# tsc.net
KiCad netlist of a schematic drawn in EAGLE
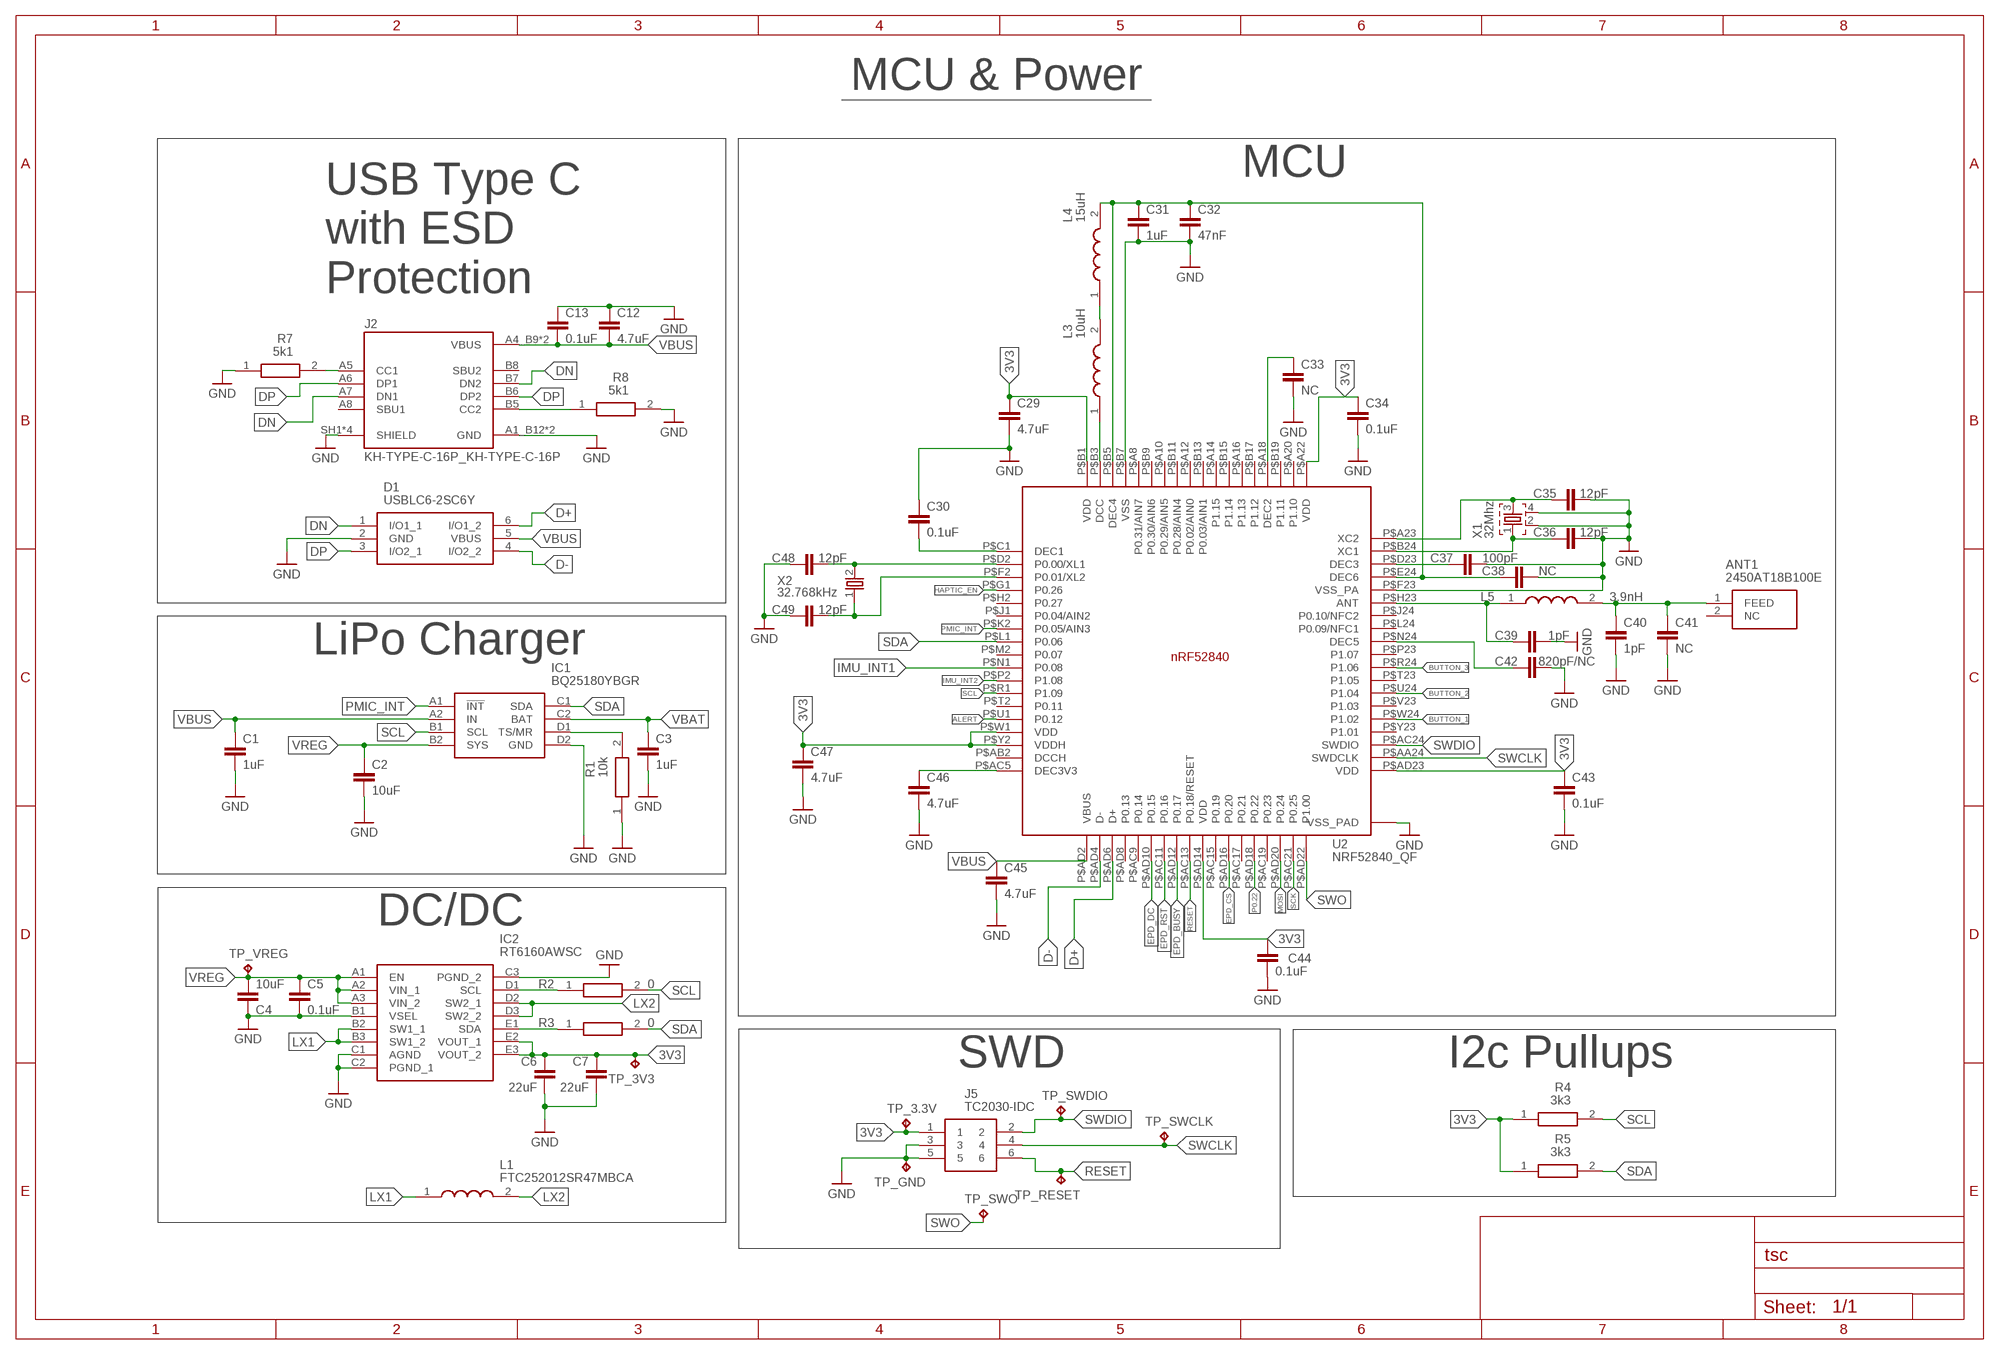
[diagram p0: schematic, sheet 1, part 1 of 2]
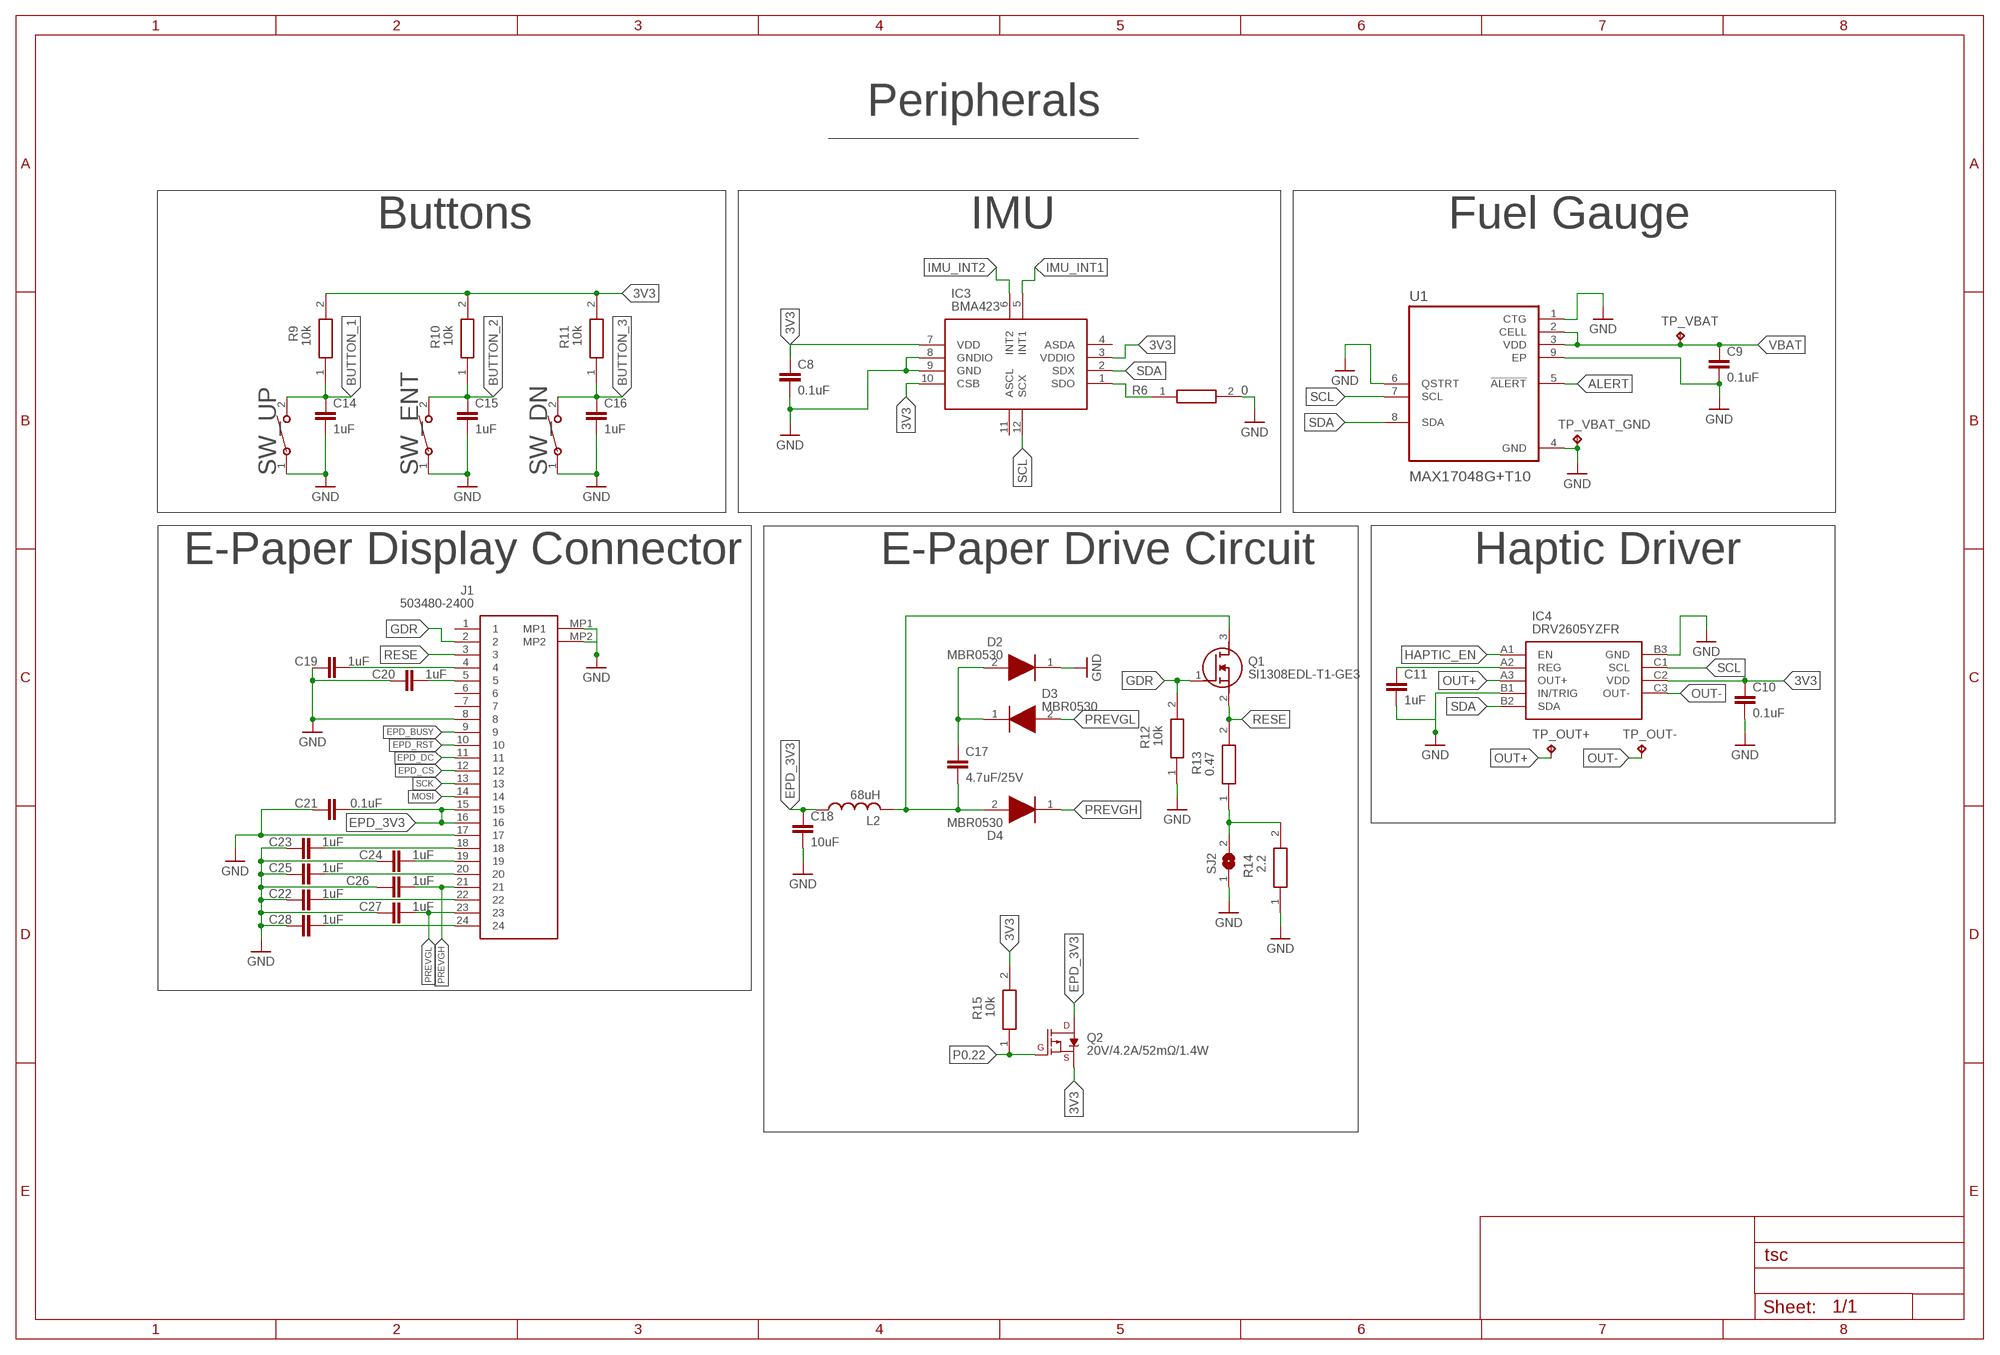
[diagram p1: schematic, sheet 1, part 2 of 2]

(export (version "E")
  (design (tool "Eeschema 10.0.6"))
  (components
    (comp (ref "ANT1")
      (value "2450AT18B100E")
      (footprint "eagle-import:2450AT18B100E_ANTC3216X140N")
      (fields (field (name "MOUSER_PART_NUMBER") "609-2450AT18B100E"))
      (libsource (lib "eagle-import") (part "2450AT18B100E_2450AT18B100E"))
    )
    (comp (ref "C1")
      (value "1uF")
      (footprint "eagle-import:NORDIC_NRF_3_RESC0402_N")
      (libsource (lib "eagle-import") (part "NORDIC_NRF_3_CAPACITOR_0402_N"))
    )
    (comp (ref "C2")
      (value "10uF")
      (footprint "eagle-import:NORDIC_NRF_3_RESC0402_N")
      (libsource (lib "eagle-import") (part "NORDIC_NRF_3_CAPACITOR_0402_N"))
    )
    (comp (ref "C3")
      (value "1uF")
      (footprint "eagle-import:NORDIC_NRF_3_RESC0402_N")
      (libsource (lib "eagle-import") (part "NORDIC_NRF_3_CAPACITOR_0402_N"))
    )
    (comp (ref "C4")
      (value "10uF")
      (footprint "eagle-import:NORDIC_NRF_3_RESC0402_N")
      (libsource (lib "eagle-import") (part "NORDIC_NRF_3_CAPACITOR_0402_N"))
    )
    (comp (ref "C5")
      (value "0.1uF")
      (footprint "eagle-import:NORDIC_NRF_3_RESC0201_N")
      (libsource (lib "eagle-import") (part "NORDIC_NRF_3_CAPACITOR_0201_N"))
    )
    (comp (ref "C6")
      (value "22uF")
      (footprint "eagle-import:NORDIC_NRF_3_RESC0402_N")
      (libsource (lib "eagle-import") (part "NORDIC_NRF_3_CAPACITOR_0402_N"))
    )
    (comp (ref "C7")
      (value "22uF")
      (footprint "eagle-import:NORDIC_NRF_3_RESC0402_N")
      (libsource (lib "eagle-import") (part "NORDIC_NRF_3_CAPACITOR_0402_N"))
    )
    (comp (ref "C8")
      (value "0.1uF")
      (footprint "eagle-import:NORDIC_NRF_3_RESC0201_N")
      (libsource (lib "eagle-import") (part "NORDIC_NRF_3_CAPACITOR_0201_N"))
    )
    (comp (ref "C9")
      (value "0.1uF")
      (footprint "eagle-import:NORDIC_NRF_3_RESC0201_N")
      (libsource (lib "eagle-import") (part "NORDIC_NRF_3_CAPACITOR_0201_N"))
    )
    (comp (ref "C10")
      (value "0.1uF")
      (footprint "eagle-import:NORDIC_NRF_3_RESC0201_N")
      (libsource (lib "eagle-import") (part "NORDIC_NRF_3_CAPACITOR_0201_N"))
    )
    (comp (ref "C11")
      (value "1uF")
      (footprint "eagle-import:NORDIC_NRF_3_RESC0402_N")
      (libsource (lib "eagle-import") (part "NORDIC_NRF_3_CAPACITOR_0402_N"))
    )
    (comp (ref "C12")
      (value "4.7uF")
      (footprint "eagle-import:NORDIC_NRF_3_RESC0402_N")
      (libsource (lib "eagle-import") (part "NORDIC_NRF_3_CAPACITOR_0402_N"))
    )
    (comp (ref "C13")
      (value "0.1uF")
      (footprint "eagle-import:NORDIC_NRF_3_RESC0201_N")
      (libsource (lib "eagle-import") (part "NORDIC_NRF_3_CAPACITOR_0201_N"))
    )
    (comp (ref "C14")
      (value "1uF")
      (footprint "eagle-import:NORDIC_NRF_3_RESC0402_N")
      (libsource (lib "eagle-import") (part "NORDIC_NRF_3_CAPACITOR_0402_N"))
    )
    (comp (ref "C15")
      (value "1uF")
      (footprint "eagle-import:NORDIC_NRF_3_RESC0402_N")
      (libsource (lib "eagle-import") (part "NORDIC_NRF_3_CAPACITOR_0402_N"))
    )
    (comp (ref "C16")
      (value "1uF")
      (footprint "eagle-import:NORDIC_NRF_3_RESC0402_N")
      (libsource (lib "eagle-import") (part "NORDIC_NRF_3_CAPACITOR_0402_N"))
    )
    (comp (ref "C17")
      (value "4.7uF/25V")
      (footprint "eagle-import:NORDIC_NRF_3_RESC0402_N")
      (libsource (lib "eagle-import") (part "NORDIC_NRF_3_CAPACITOR_0402_N"))
    )
    (comp (ref "C18")
      (value "10uF")
      (footprint "eagle-import:NORDIC_NRF_3_RESC0402_N")
      (libsource (lib "eagle-import") (part "NORDIC_NRF_3_CAPACITOR_0402_N"))
    )
    (comp (ref "C19")
      (value "1uF")
      (footprint "eagle-import:NORDIC_NRF_3_RESC0402_N")
      (libsource (lib "eagle-import") (part "NORDIC_NRF_3_CAPACITOR_0402_N"))
    )
    (comp (ref "C20")
      (value "1uF")
      (footprint "eagle-import:NORDIC_NRF_3_RESC0402_N")
      (libsource (lib "eagle-import") (part "NORDIC_NRF_3_CAPACITOR_0402_N"))
    )
    (comp (ref "C21")
      (value "0.1uF")
      (footprint "eagle-import:NORDIC_NRF_3_RESC0201_N")
      (libsource (lib "eagle-import") (part "NORDIC_NRF_3_CAPACITOR_0201_N"))
    )
    (comp (ref "C22")
      (value "1uF")
      (footprint "eagle-import:NORDIC_NRF_3_RESC0402_N")
      (libsource (lib "eagle-import") (part "NORDIC_NRF_3_CAPACITOR_0402_N"))
    )
    (comp (ref "C23")
      (value "1uF")
      (footprint "eagle-import:NORDIC_NRF_3_RESC0402_N")
      (libsource (lib "eagle-import") (part "NORDIC_NRF_3_CAPACITOR_0402_N"))
    )
    (comp (ref "C24")
      (value "1uF")
      (footprint "eagle-import:NORDIC_NRF_3_RESC0402_N")
      (libsource (lib "eagle-import") (part "NORDIC_NRF_3_CAPACITOR_0402_N"))
    )
    (comp (ref "C25")
      (value "1uF")
      (footprint "eagle-import:NORDIC_NRF_3_RESC0402_N")
      (libsource (lib "eagle-import") (part "NORDIC_NRF_3_CAPACITOR_0402_N"))
    )
    (comp (ref "C26")
      (value "1uF")
      (footprint "eagle-import:NORDIC_NRF_3_RESC0402_N")
      (libsource (lib "eagle-import") (part "NORDIC_NRF_3_CAPACITOR_0402_N"))
    )
    (comp (ref "C27")
      (value "1uF")
      (footprint "eagle-import:NORDIC_NRF_3_RESC0402_N")
      (libsource (lib "eagle-import") (part "NORDIC_NRF_3_CAPACITOR_0402_N"))
    )
    (comp (ref "C28")
      (value "1uF")
      (footprint "eagle-import:NORDIC_NRF_3_RESC0402_N")
      (libsource (lib "eagle-import") (part "NORDIC_NRF_3_CAPACITOR_0402_N"))
    )
    (comp (ref "C29")
      (value "4.7uF")
      (footprint "eagle-import:NORDIC_NRF_3_RESC0402_N")
      (libsource (lib "eagle-import") (part "NORDIC_NRF_3_CAPACITOR_0402_N"))
    )
    (comp (ref "C30")
      (value "0.1uF")
      (footprint "eagle-import:NORDIC_NRF_3_RESC0201_N")
      (libsource (lib "eagle-import") (part "NORDIC_NRF_3_CAPACITOR_0201_N"))
    )
    (comp (ref "C31")
      (value "1uF")
      (footprint "eagle-import:NORDIC_NRF_3_RESC0402_N")
      (libsource (lib "eagle-import") (part "NORDIC_NRF_3_CAPACITOR_0402_N"))
    )
    (comp (ref "C32")
      (value "47nF")
      (footprint "eagle-import:NORDIC_NRF_3_RESC0201_N")
      (libsource (lib "eagle-import") (part "NORDIC_NRF_3_CAPACITOR_0201_N"))
    )
    (comp (ref "C33")
      (value "NC")
      (footprint "eagle-import:NORDIC_NRF_3_RESC0201_N")
      (libsource (lib "eagle-import") (part "NORDIC_NRF_3_CAPACITOR_0201_N"))
    )
    (comp (ref "C34")
      (value "0.1uF")
      (footprint "eagle-import:NORDIC_NRF_3_RESC0201_N")
      (libsource (lib "eagle-import") (part "NORDIC_NRF_3_CAPACITOR_0201_N"))
    )
    (comp (ref "C35")
      (value "12pF")
      (footprint "eagle-import:NORDIC_NRF_3_RESC0201_N")
      (libsource (lib "eagle-import") (part "NORDIC_NRF_3_CAPACITOR_0201_N"))
    )
    (comp (ref "C36")
      (value "12pF")
      (footprint "eagle-import:NORDIC_NRF_3_RESC0201_N")
      (libsource (lib "eagle-import") (part "NORDIC_NRF_3_CAPACITOR_0201_N"))
    )
    (comp (ref "C37")
      (value "100pF")
      (footprint "eagle-import:NORDIC_NRF_3_RESC0201_N")
      (libsource (lib "eagle-import") (part "NORDIC_NRF_3_CAPACITOR_0201_N"))
    )
    (comp (ref "C38")
      (value "NC")
      (footprint "eagle-import:NORDIC_NRF_3_RESC0201_N")
      (libsource (lib "eagle-import") (part "NORDIC_NRF_3_CAPACITOR_0201_N"))
    )
    (comp (ref "C39")
      (value "1pF")
      (footprint "eagle-import:NORDIC_NRF_3_RESC0201_N")
      (libsource (lib "eagle-import") (part "NORDIC_NRF_3_CAPACITOR_0201_N"))
    )
    (comp (ref "C40")
      (value "1pF")
      (footprint "eagle-import:NORDIC_NRF_3_RESC0201_N")
      (libsource (lib "eagle-import") (part "NORDIC_NRF_3_CAPACITOR_0201_N"))
    )
    (comp (ref "C41")
      (value "NC")
      (footprint "eagle-import:NORDIC_NRF_3_RESC0201_N")
      (libsource (lib "eagle-import") (part "NORDIC_NRF_3_CAPACITOR_0201_N"))
    )
    (comp (ref "C42")
      (value "820pF/NC")
      (footprint "eagle-import:NORDIC_NRF_3_RESC0201_N")
      (libsource (lib "eagle-import") (part "NORDIC_NRF_3_CAPACITOR_0201_N"))
    )
    (comp (ref "C43")
      (value "0.1uF")
      (footprint "eagle-import:NORDIC_NRF_3_RESC0201_N")
      (libsource (lib "eagle-import") (part "NORDIC_NRF_3_CAPACITOR_0201_N"))
    )
    (comp (ref "C44")
      (value "0.1uF")
      (footprint "eagle-import:NORDIC_NRF_3_RESC0201_N")
      (libsource (lib "eagle-import") (part "NORDIC_NRF_3_CAPACITOR_0201_N"))
    )
    (comp (ref "C45")
      (value "4.7uF")
      (footprint "eagle-import:NORDIC_NRF_3_RESC0402_N")
      (libsource (lib "eagle-import") (part "NORDIC_NRF_3_CAPACITOR_0402_N"))
    )
    (comp (ref "C46")
      (value "4.7uF")
      (footprint "eagle-import:NORDIC_NRF_3_RESC0402_N")
      (libsource (lib "eagle-import") (part "NORDIC_NRF_3_CAPACITOR_0402_N"))
    )
    (comp (ref "C47")
      (value "4.7uF")
      (footprint "eagle-import:NORDIC_NRF_3_RESC0402_N")
      (libsource (lib "eagle-import") (part "NORDIC_NRF_3_CAPACITOR_0402_N"))
    )
    (comp (ref "C48")
      (value "12pF")
      (footprint "eagle-import:NORDIC_NRF_3_RESC0201_N")
      (libsource (lib "eagle-import") (part "NORDIC_NRF_3_CAPACITOR_0201_N"))
    )
    (comp (ref "C49")
      (value "12pF")
      (footprint "eagle-import:NORDIC_NRF_3_RESC0201_N")
      (libsource (lib "eagle-import") (part "NORDIC_NRF_3_CAPACITOR_0201_N"))
    )
    (comp (ref "D1")
      (value "USBLC6-2SC6Y")
      (footprint "eagle-import:ESP32_C6_LIBRARY_3_SOT95P280X145-6N")
      (fields (field (name "MF") "STMicroelectronics"))
      (libsource (lib "eagle-import") (part "ESP32_C6_LIBRARY_3_USBLC6-2SC6Y"))
    )
    (comp (ref "D2")
      (value "MBR0530")
      (footprint "eagle-import:ESP32_C6_LIBRARY_5_SOD3716X135N")
      (fields (field (name "MF") "ON Semiconductor"))
      (libsource (lib "eagle-import") (part "ESP32_C6_LIBRARY_5_MBR0530"))
    )
    (comp (ref "D3")
      (value "MBR0530")
      (footprint "eagle-import:ESP32_C6_LIBRARY_5_SOD3716X135N")
      (fields (field (name "MF") "ON Semiconductor"))
      (libsource (lib "eagle-import") (part "ESP32_C6_LIBRARY_5_MBR0530"))
    )
    (comp (ref "D4")
      (value "MBR0530")
      (footprint "eagle-import:ESP32_C6_LIBRARY_5_SOD3716X135N")
      (fields (field (name "MF") "ON Semiconductor"))
      (libsource (lib "eagle-import") (part "ESP32_C6_LIBRARY_5_MBR0530"))
    )
    (comp (ref "IC1")
      (value "BQ25180YBGR")
      (footprint "eagle-import:BQ25180YBGR_BGA8C40P2X4_100X155X50")
      (fields (field (name "MOUSER_PART_NUMBER") "595-BQ25180YBGR"))
      (libsource (lib "eagle-import") (part "BQ25180YBGR_BQ25180YBGR"))
    )
    (comp (ref "IC2")
      (value "RT6160AWSC")
      (footprint "eagle-import:RT6160AWSC_BGA15C40P3X5_140X230X60")
      (fields (field (name "MOUSER_PART_NUMBER") "835-RT6160AWSC"))
      (libsource (lib "eagle-import") (part "RT6160AWSC_RT6160AWSC"))
    )
    (comp (ref "IC3")
      (value "BMA423")
      (footprint "eagle-import:BMA423_BMA423")
      (fields (field (name "MOUSER_PART_NUMBER") "262-BMA423"))
      (libsource (lib "eagle-import") (part "BMA423_BMA423"))
    )
    (comp (ref "IC4")
      (value "DRV2605YZFR")
      (footprint "eagle-import:DRV2605YZFR_BGA9C50P3X3_144X144X62")
      (libsource (lib "eagle-import") (part "DRV2605YZFR_DRV2605YZFR"))
    )
    (comp (ref "J1")
      (value "503480-2400")
      (footprint "eagle-import:503480-2400_5034802400")
      (fields (field (name "MOUSER_PART_NUMBER") "538-503480-2400"))
      (libsource (lib "eagle-import") (part "503480-2400_503480-2400"))
    )
    (comp (ref "J2")
      (value "KH-TYPE-C-16P_KH-TYPE-C-16P")
      (footprint "eagle-import:KH-TYPE-C-16P_KINGHELM_KH-TYPE-C-16P")
      (fields (field (name "MF") "kinghelm") (field (name "MP") "KH-TYPE-C-16P"))
      (libsource (lib "eagle-import") (part "KH-TYPE-C-16P_KH-TYPE-C-16P"))
    )
    (comp (ref "J5")
      (value "TC2030-IDC")
      (footprint "eagle-import:TC2030-IDC_TC2030IDC")
      (libsource (lib "eagle-import") (part "TC2030-IDC_TC2030-IDC"))
    )
    (comp (ref "L1")
      (value "FTC252012SR47MBCA")
      (footprint "eagle-import:MLP2016SR47MT0S1_INDC2016X100N")
      (libsource (lib "eagle-import") (part "MLP2016SR47MT0S1_FTC252012SR47MBCA"))
    )
    (comp (ref "L2")
      (value "68uH")
      (footprint "eagle-import:NORDIC_NRF_2_RESC0402_L")
      (libsource (lib "eagle-import") (part "NORDIC_NRF_2_INDUCTOR_0402_L"))
    )
    (comp (ref "L3")
      (value "10uH")
      (footprint "eagle-import:MLP2016SR47MT0S1_INDC2016X100N")
      (fields (field (name "MANUFACTURER_PART_NUMBER") "FTC252012SR47MBCA"))
      (libsource (lib "eagle-import") (part "MLP2016SR47MT0S1_FTC252012SR47MBCA"))
    )
    (comp (ref "L4")
      (value "15uH")
      (footprint "eagle-import:MLP2016SR47MT0S1_INDC2016X100N")
      (fields (field (name "MANUFACTURER_PART_NUMBER") "FTC252012SR47MBCA"))
      (libsource (lib "eagle-import") (part "MLP2016SR47MT0S1_FTC252012SR47MBCA"))
    )
    (comp (ref "L5")
      (value "3.9nH")
      (footprint "eagle-import:MLP2016SR47MT0S1_INDC2016X100N")
      (fields (field (name "MANUFACTURER_PART_NUMBER") "FTC252012SR47MBCA"))
      (libsource (lib "eagle-import") (part "MLP2016SR47MT0S1_FTC252012SR47MBCA"))
    )
    (comp (ref "Q1")
      (value "SI1308EDL-T1-GE3")
      (footprint "eagle-import:ESP32_C6_LIBRARY_6_SOT65P210X110-3N")
      (fields (field (name "MF") "Vishay Siliconix"))
      (libsource (lib "eagle-import") (part "ESP32_C6_LIBRARY_6_SI1308EDL-T1-GE3"))
    )
    (comp (ref "Q2")
      (value "20V/4.2A/52mΩ/1.4W")
      (footprint "eagle-import:ESP32_C6_LIBRARY_4_ESP32_C6_LIBRARY_4_ESP32_C6_LIBRARY_4_ESP32_C6_LIBRARY_4_ESP32_WROVER_SPARKFUN-DISCRETESEMI_SOT23-3")
      (libsource (lib "eagle-import") (part "ESP32_C6_LIBRARY_4_ESP32_WROVER_SPARKFUN-DISCRETESEMI_MOSFET_PCH-DMG2305UX-7"))
    )
    (comp (ref "R1")
      (value "10k")
      (footprint "eagle-import:CPF0201D7K68C1_0201")
      (libsource (lib "eagle-import") (part "CPF0201D7K68C1_CPF0201D7K68C1"))
    )
    (comp (ref "R2")
      (value "0")
      (footprint "eagle-import:CPF0201D7K68C1_0201")
      (libsource (lib "eagle-import") (part "CPF0201D7K68C1_CPF0201D7K68C1"))
    )
    (comp (ref "R3")
      (value "0")
      (footprint "eagle-import:CPF0201D7K68C1_0201")
      (libsource (lib "eagle-import") (part "CPF0201D7K68C1_CPF0201D7K68C1"))
    )
    (comp (ref "R4")
      (value "3k3")
      (footprint "eagle-import:CPF0201D7K68C1_0201")
      (libsource (lib "eagle-import") (part "CPF0201D7K68C1_CPF0201D7K68C1"))
    )
    (comp (ref "R5")
      (value "3k3")
      (footprint "eagle-import:CPF0201D7K68C1_0201")
      (libsource (lib "eagle-import") (part "CPF0201D7K68C1_CPF0201D7K68C1"))
    )
    (comp (ref "R6")
      (value "0")
      (footprint "eagle-import:CPF0201D7K68C1_0201")
      (libsource (lib "eagle-import") (part "CPF0201D7K68C1_CPF0201D7K68C1"))
    )
    (comp (ref "R7")
      (value "5k1")
      (footprint "eagle-import:CPF0201D7K68C1_0201")
      (libsource (lib "eagle-import") (part "CPF0201D7K68C1_CPF0201D7K68C1"))
    )
    (comp (ref "R8")
      (value "5k1")
      (footprint "eagle-import:CPF0201D7K68C1_0201")
      (libsource (lib "eagle-import") (part "CPF0201D7K68C1_CPF0201D7K68C1"))
    )
    (comp (ref "R9")
      (value "10k")
      (footprint "eagle-import:CPF0201D7K68C1_0201")
      (libsource (lib "eagle-import") (part "CPF0201D7K68C1_CPF0201D7K68C1"))
    )
    (comp (ref "R10")
      (value "10k")
      (footprint "eagle-import:CPF0201D7K68C1_0201")
      (libsource (lib "eagle-import") (part "CPF0201D7K68C1_CPF0201D7K68C1"))
    )
    (comp (ref "R11")
      (value "10k")
      (footprint "eagle-import:CPF0201D7K68C1_0201")
      (libsource (lib "eagle-import") (part "CPF0201D7K68C1_CPF0201D7K68C1"))
    )
    (comp (ref "R12")
      (value "10k")
      (footprint "eagle-import:CPF0201D7K68C1_0201")
      (libsource (lib "eagle-import") (part "CPF0201D7K68C1_CPF0201D7K68C1"))
    )
    (comp (ref "R13")
      (value "0.47")
      (footprint "eagle-import:CPF0201D7K68C1_0201")
      (libsource (lib "eagle-import") (part "CPF0201D7K68C1_CPF0201D7K68C1"))
    )
    (comp (ref "R14")
      (value "2.2")
      (footprint "eagle-import:CPF0201D7K68C1_0201")
      (libsource (lib "eagle-import") (part "CPF0201D7K68C1_CPF0201D7K68C1"))
    )
    (comp (ref "R15")
      (value "10k")
      (footprint "eagle-import:CPF0201D7K68C1_0201")
      (libsource (lib "eagle-import") (part "CPF0201D7K68C1_CPF0201D7K68C1"))
    )
    (comp (ref "SJ2")
      (value "-")
      (footprint "eagle-import:ESP32_C6_LIBRARY_7_JUMPER_SJ")
      (libsource (lib "eagle-import") (part "ESP32_C6_LIBRARY_7_JUMPER_SJ"))
    )
    (comp (ref "SW_DN")
      (value "2025-10-22_07-23-44_LIBRARY_EVP-AKE31ASW_EVP-AKE31A_PAN")
      (footprint "eagle-import:2025-10-22_07-23-44_LIBRARY_SW_EVP-AKE31A_PAN")
      (fields
        (field (name "MANUFACTURER_PART_NUMBER") "EVP-AKE31A")
        (field (name "COPYRIGHT") "Copyright (C) 2025 Ultra Librarian. All rights reserved.")
      )
      (libsource (lib "eagle-import") (part "2025-10-22_07-23-44_LIBRARY_EVP-AKE31ASW_EVP-AKE31A_PAN"))
    )
    (comp (ref "SW_ENT")
      (value "2025-10-22_07-23-44_LIBRARY_EVP-AKE31ASW_EVP-AKE31A_PAN")
      (footprint "eagle-import:2025-10-22_07-23-44_LIBRARY_SW_EVP-AKE31A_PAN")
      (fields
        (field (name "MANUFACTURER_PART_NUMBER") "EVP-AKE31A")
        (field (name "COPYRIGHT") "Copyright (C) 2025 Ultra Librarian. All rights reserved.")
      )
      (libsource (lib "eagle-import") (part "2025-10-22_07-23-44_LIBRARY_EVP-AKE31ASW_EVP-AKE31A_PAN"))
    )
    (comp (ref "SW_UP")
      (value "2025-10-22_07-23-44_LIBRARY_EVP-AKE31ASW_EVP-AKE31A_PAN")
      (footprint "eagle-import:2025-10-22_07-23-44_LIBRARY_SW_EVP-AKE31A_PAN")
      (fields
        (field (name "MANUFACTURER_PART_NUMBER") "EVP-AKE31A")
        (field (name "COPYRIGHT") "Copyright (C) 2025 Ultra Librarian. All rights reserved.")
      )
      (libsource (lib "eagle-import") (part "2025-10-22_07-23-44_LIBRARY_EVP-AKE31ASW_EVP-AKE31A_PAN"))
    )
    (comp (ref "TP_3.3V")
      (value "HECTOR_WATCH_1_TPTP20R")
      (footprint "eagle-import:HECTOR_WATCH_1_TP20R")
      (libsource (lib "eagle-import") (part "HECTOR_WATCH_1_TPTP20R"))
    )
    (comp (ref "TP_3V3")
      (value "HECTOR_WATCH_1_TPTP20R")
      (footprint "eagle-import:HECTOR_WATCH_1_TP20R")
      (libsource (lib "eagle-import") (part "HECTOR_WATCH_1_TPTP20R"))
    )
    (comp (ref "TP_GND")
      (value "HECTOR_WATCH_1_TPTP20R")
      (footprint "eagle-import:HECTOR_WATCH_1_TP20R")
      (libsource (lib "eagle-import") (part "HECTOR_WATCH_1_TPTP20R"))
    )
    (comp (ref "TP_OUT+")
      (value "HECTOR_WATCH_1_TPTP20R")
      (footprint "eagle-import:HECTOR_WATCH_1_TP20R")
      (libsource (lib "eagle-import") (part "HECTOR_WATCH_1_TPTP20R"))
    )
    (comp (ref "TP_OUT-")
      (value "HECTOR_WATCH_1_TPTP20R")
      (footprint "eagle-import:HECTOR_WATCH_1_TP20R")
      (libsource (lib "eagle-import") (part "HECTOR_WATCH_1_TPTP20R"))
    )
    (comp (ref "TP_RESET")
      (value "HECTOR_WATCH_1_TPTP20R")
      (footprint "eagle-import:HECTOR_WATCH_1_TP20R")
      (libsource (lib "eagle-import") (part "HECTOR_WATCH_1_TPTP20R"))
    )
    (comp (ref "TP_SWCLK")
      (value "HECTOR_WATCH_1_TPTP20R")
      (footprint "eagle-import:HECTOR_WATCH_1_TP20R")
      (libsource (lib "eagle-import") (part "HECTOR_WATCH_1_TPTP20R"))
    )
    (comp (ref "TP_SWDIO")
      (value "HECTOR_WATCH_1_TPTP20R")
      (footprint "eagle-import:HECTOR_WATCH_1_TP20R")
      (libsource (lib "eagle-import") (part "HECTOR_WATCH_1_TPTP20R"))
    )
    (comp (ref "TP_SWO")
      (value "HECTOR_WATCH_1_TPTP20R")
      (footprint "eagle-import:HECTOR_WATCH_1_TP20R")
      (libsource (lib "eagle-import") (part "HECTOR_WATCH_1_TPTP20R"))
    )
    (comp (ref "TP_VBAT")
      (value "HECTOR_WATCH_1_TPTP20R")
      (footprint "eagle-import:HECTOR_WATCH_1_TP20R")
      (libsource (lib "eagle-import") (part "HECTOR_WATCH_1_TPTP20R"))
    )
    (comp (ref "TP_VBAT_GND")
      (value "HECTOR_WATCH_1_TPTP20R")
      (footprint "eagle-import:HECTOR_WATCH_1_TP20R")
      (libsource (lib "eagle-import") (part "HECTOR_WATCH_1_TPTP20R"))
    )
    (comp (ref "TP_VREG")
      (value "HECTOR_WATCH_1_TPTP20R")
      (footprint "eagle-import:HECTOR_WATCH_1_TP20R")
      (libsource (lib "eagle-import") (part "HECTOR_WATCH_1_TPTP20R"))
    )
    (comp (ref "U1")
      (value "MAX17048G+T10")
      (footprint "eagle-import:ESP32_C6_LIBRARY_SON50P200X200X80-9N")
      (fields (field (name "MF") "Analog Devices"))
      (libsource (lib "eagle-import") (part "ESP32_C6_LIBRARY_MAX17048G+T10"))
    )
    (comp (ref "U2")
      (value "NRF52840_QF")
      (footprint "eagle-import:NORDIC_NRF_4_AQFN50P700X700X85_HS-74N")
      (libsource (lib "eagle-import") (part "NORDIC_NRF_4_NRF52840_QF"))
    )
    (comp (ref "X1")
      (value "32Mhz")
      (footprint "eagle-import:NORDIC_NRF_BT-XTAL_2016_N")
      (libsource (lib "eagle-import") (part "NORDIC_NRF_XTAL_32MHZ"))
    )
    (comp (ref "X2")
      (value "32.768kHz")
      (footprint "eagle-import:NORDIC_NRF_1_XTAL_3215_N")
      (libsource (lib "eagle-import") (part "NORDIC_NRF_1_XTAL_32KHZ"))
    )
  )
  (nets
    (net (code "1") (name "3V3") (class "Default")
      (node (ref "C10") (pin "1") (pinfunction "1_1") (pintype "passive"))
      (node (ref "C29") (pin "1") (pinfunction "1_1") (pintype "passive"))
      (node (ref "C34") (pin "1") (pinfunction "1_1") (pintype "passive"))
      (node (ref "C43") (pin "1") (pinfunction "1_1") (pintype "passive"))
      (node (ref "C44") (pin "1") (pinfunction "1_1") (pintype "passive"))
      (node (ref "C47") (pin "1") (pinfunction "1_1") (pintype "passive"))
      (node (ref "C6") (pin "1") (pinfunction "1_1") (pintype "passive"))
      (node (ref "C7") (pin "1") (pinfunction "1_1") (pintype "passive"))
      (node (ref "C8") (pin "1") (pinfunction "1_1") (pintype "passive"))
      (node (ref "IC2") (pin "E2") (pinfunction "VOUT_1_E2") (pintype "bidirectional"))
      (node (ref "IC2") (pin "E3") (pinfunction "VOUT_2_E3") (pintype "bidirectional"))
      (node (ref "IC3") (pin "10") (pinfunction "CSB_10") (pintype "bidirectional"))
      (node (ref "IC3") (pin "3") (pinfunction "VDDIO_3") (pintype "bidirectional"))
      (node (ref "IC3") (pin "7") (pinfunction "VDD_7") (pintype "bidirectional"))
      (node (ref "IC4") (pin "C2") (pinfunction "VDD_C2") (pintype "bidirectional"))
      (node (ref "J5") (pin "1") (pinfunction "1_1") (pintype "bidirectional"))
      (node (ref "Q2") (pin "2") (pinfunction "S_2") (pintype "bidirectional"))
      (node (ref "R10") (pin "2") (pinfunction "2_2") (pintype "bidirectional"))
      (node (ref "R11") (pin "2") (pinfunction "2_2") (pintype "bidirectional"))
      (node (ref "R15") (pin "2") (pinfunction "2_2") (pintype "bidirectional"))
      (node (ref "R4") (pin "1") (pinfunction "1_1") (pintype "bidirectional"))
      (node (ref "R5") (pin "1") (pinfunction "1_1") (pintype "bidirectional"))
      (node (ref "R9") (pin "2") (pinfunction "2_2") (pintype "bidirectional"))
      (node (ref "TP_3.3V") (pin "TP") (pinfunction "TP_TP") (pintype "input"))
      (node (ref "TP_3V3") (pin "TP") (pinfunction "TP_TP") (pintype "input"))
      (node (ref "U2") (pin "P$A22") (pinfunction "VDD_P$A22") (pintype "power_in"))
      (node (ref "U2") (pin "P$AD14") (pinfunction "VDD_P$AD14") (pintype "power_in"))
      (node (ref "U2") (pin "P$AD23") (pinfunction "VDD_P$AD23") (pintype "power_in"))
      (node (ref "U2") (pin "P$B1") (pinfunction "VDD_P$B1") (pintype "power_in"))
      (node (ref "U2") (pin "P$W1") (pinfunction "VDD_P$W1") (pintype "power_in"))
      (node (ref "U2") (pin "P$Y2") (pinfunction "VDDH_P$Y2") (pintype "power_in"))
    )
    (net (code "2") (name "ALERT") (class "Default")
      (node (ref "U1") (pin "5") (pinfunction "~{ALERT}_5") (pintype "output"))
      (node (ref "U2") (pin "P$U1") (pinfunction "P0.12_P$U1") (pintype "bidirectional"))
    )
    (net (code "3") (name "BUTTON_1") (class "Default")
      (node (ref "C14") (pin "1") (pinfunction "1_1") (pintype "passive"))
      (node (ref "R9") (pin "1") (pinfunction "1_1") (pintype "bidirectional"))
      (node (ref "SW_UP") (pin "2") (pinfunction "2_2") (pintype "passive"))
      (node (ref "U2") (pin "P$W24") (pinfunction "P1.02_P$W24") (pintype "bidirectional"))
    )
    (net (code "4") (name "BUTTON_2") (class "Default")
      (node (ref "C15") (pin "1") (pinfunction "1_1") (pintype "passive"))
      (node (ref "R10") (pin "1") (pinfunction "1_1") (pintype "bidirectional"))
      (node (ref "SW_ENT") (pin "2") (pinfunction "2_2") (pintype "passive"))
      (node (ref "U2") (pin "P$U24") (pinfunction "P1.04_P$U24") (pintype "bidirectional"))
    )
    (net (code "5") (name "BUTTON_3") (class "Default")
      (node (ref "C16") (pin "1") (pinfunction "1_1") (pintype "passive"))
      (node (ref "R11") (pin "1") (pinfunction "1_1") (pintype "bidirectional"))
      (node (ref "SW_DN") (pin "2") (pinfunction "2_2") (pintype "passive"))
      (node (ref "U2") (pin "P$R24") (pinfunction "P1.06_P$R24") (pintype "bidirectional"))
    )
    (net (code "6") (name "D+") (class "Default")
      (node (ref "D1") (pin "6") (pinfunction "I/O1_2_6") (pintype "bidirectional"))
      (node (ref "U2") (pin "P$AD6") (pinfunction "D+_P$AD6") (pintype "bidirectional"))
    )
    (net (code "7") (name "D-") (class "Default")
      (node (ref "D1") (pin "4") (pinfunction "I/O2_2_4") (pintype "bidirectional"))
      (node (ref "U2") (pin "P$AD4") (pinfunction "D-_P$AD4") (pintype "bidirectional"))
    )
    (net (code "8") (name "DN") (class "Default")
      (node (ref "D1") (pin "1") (pinfunction "I/O1_1_1") (pintype "bidirectional"))
      (node (ref "J2") (pin "A7") (pinfunction "DN1_A7") (pintype "bidirectional"))
      (node (ref "J2") (pin "B7") (pinfunction "DN2_B7") (pintype "bidirectional"))
    )
    (net (code "9") (name "DP") (class "Default")
      (node (ref "D1") (pin "3") (pinfunction "I/O2_1_3") (pintype "bidirectional"))
      (node (ref "J2") (pin "A6") (pinfunction "DP1_A6") (pintype "bidirectional"))
      (node (ref "J2") (pin "B6") (pinfunction "DP2_B6") (pintype "bidirectional"))
    )
    (net (code "10") (name "EPD_3V3") (class "Default")
      (node (ref "C18") (pin "1") (pinfunction "1_1") (pintype "passive"))
      (node (ref "C21") (pin "2") (pinfunction "2_2") (pintype "passive"))
      (node (ref "J1") (pin "15") (pinfunction "15_15") (pintype "bidirectional"))
      (node (ref "J1") (pin "16") (pinfunction "16_16") (pintype "bidirectional"))
      (node (ref "L2") (pin "1") (pinfunction "1_1") (pintype "passive"))
      (node (ref "Q2") (pin "3") (pinfunction "D_3") (pintype "bidirectional"))
    )
    (net (code "11") (name "EPD_BUSY") (class "Default")
      (node (ref "J1") (pin "9") (pinfunction "9_9") (pintype "bidirectional"))
      (node (ref "U2") (pin "P$AD12") (pinfunction "P0.17_P$AD12") (pintype "bidirectional"))
    )
    (net (code "12") (name "EPD_CS") (class "Default")
      (node (ref "J1") (pin "12") (pinfunction "12_12") (pintype "bidirectional"))
      (node (ref "U2") (pin "P$AD16") (pinfunction "P0.20_P$AD16") (pintype "bidirectional"))
    )
    (net (code "13") (name "EPD_DC") (class "Default")
      (node (ref "J1") (pin "11") (pinfunction "11_11") (pintype "bidirectional"))
      (node (ref "U2") (pin "P$AD10") (pinfunction "P0.15_P$AD10") (pintype "bidirectional"))
    )
    (net (code "14") (name "EPD_RST") (class "Default")
      (node (ref "J1") (pin "10") (pinfunction "10_10") (pintype "bidirectional"))
      (node (ref "U2") (pin "P$AC11") (pinfunction "P0.16_P$AC11") (pintype "bidirectional"))
    )
    (net (code "15") (name "GDR") (class "Default")
      (node (ref "J1") (pin "2") (pinfunction "2_2") (pintype "bidirectional"))
      (node (ref "Q1") (pin "1") (pinfunction "G_1") (pintype "bidirectional"))
      (node (ref "R12") (pin "2") (pinfunction "2_2") (pintype "bidirectional"))
    )
    (net (code "16") (name "GND") (class "Default")
      (node (ref "C1") (pin "2") (pinfunction "2_2") (pintype "passive"))
      (node (ref "C10") (pin "2") (pinfunction "2_2") (pintype "passive"))
      (node (ref "C11") (pin "2") (pinfunction "2_2") (pintype "passive"))
      (node (ref "C12") (pin "1") (pinfunction "1_1") (pintype "passive"))
      (node (ref "C13") (pin "1") (pinfunction "1_1") (pintype "passive"))
      (node (ref "C14") (pin "2") (pinfunction "2_2") (pintype "passive"))
      (node (ref "C15") (pin "2") (pinfunction "2_2") (pintype "passive"))
      (node (ref "C16") (pin "2") (pinfunction "2_2") (pintype "passive"))
      (node (ref "C18") (pin "2") (pinfunction "2_2") (pintype "passive"))
      (node (ref "C19") (pin "1") (pinfunction "1_1") (pintype "passive"))
      (node (ref "C2") (pin "2") (pinfunction "2_2") (pintype "passive"))
      (node (ref "C20") (pin "1") (pinfunction "1_1") (pintype "passive"))
      (node (ref "C21") (pin "1") (pinfunction "1_1") (pintype "passive"))
      (node (ref "C22") (pin "1") (pinfunction "1_1") (pintype "passive"))
      (node (ref "C23") (pin "1") (pinfunction "1_1") (pintype "passive"))
      (node (ref "C24") (pin "1") (pinfunction "1_1") (pintype "passive"))
      (node (ref "C25") (pin "1") (pinfunction "1_1") (pintype "passive"))
      (node (ref "C26") (pin "1") (pinfunction "1_1") (pintype "passive"))
      (node (ref "C27") (pin "1") (pinfunction "1_1") (pintype "passive"))
      (node (ref "C28") (pin "1") (pinfunction "1_1") (pintype "passive"))
      (node (ref "C29") (pin "2") (pinfunction "2_2") (pintype "passive"))
      (node (ref "C3") (pin "2") (pinfunction "2_2") (pintype "passive"))
      (node (ref "C30") (pin "1") (pinfunction "1_1") (pintype "passive"))
      (node (ref "C31") (pin "2") (pinfunction "2_2") (pintype "passive"))
      (node (ref "C32") (pin "2") (pinfunction "2_2") (pintype "passive"))
      (node (ref "C33") (pin "2") (pinfunction "2_2") (pintype "passive"))
      (node (ref "C34") (pin "2") (pinfunction "2_2") (pintype "passive"))
      (node (ref "C35") (pin "2") (pinfunction "2_2") (pintype "passive"))
      (node (ref "C36") (pin "2") (pinfunction "2_2") (pintype "passive"))
      (node (ref "C37") (pin "2") (pinfunction "2_2") (pintype "passive"))
      (node (ref "C38") (pin "2") (pinfunction "2_2") (pintype "passive"))
      (node (ref "C39") (pin "2") (pinfunction "2_2") (pintype "passive"))
      (node (ref "C4") (pin "1") (pinfunction "1_1") (pintype "passive"))
      (node (ref "C40") (pin "2") (pinfunction "2_2") (pintype "passive"))
      (node (ref "C41") (pin "2") (pinfunction "2_2") (pintype "passive"))
      (node (ref "C42") (pin "2") (pinfunction "2_2") (pintype "passive"))
      (node (ref "C43") (pin "2") (pinfunction "2_2") (pintype "passive"))
      (node (ref "C44") (pin "2") (pinfunction "2_2") (pintype "passive"))
      (node (ref "C45") (pin "2") (pinfunction "2_2") (pintype "passive"))
      (node (ref "C46") (pin "2") (pinfunction "2_2") (pintype "passive"))
      (node (ref "C47") (pin "2") (pinfunction "2_2") (pintype "passive"))
      (node (ref "C48") (pin "1") (pinfunction "1_1") (pintype "passive"))
      (node (ref "C49") (pin "1") (pinfunction "1_1") (pintype "passive"))
      (node (ref "C5") (pin "2") (pinfunction "2_2") (pintype "passive"))
      (node (ref "C6") (pin "2") (pinfunction "2_2") (pintype "passive"))
      (node (ref "C7") (pin "2") (pinfunction "2_2") (pintype "passive"))
      (node (ref "C8") (pin "2") (pinfunction "2_2") (pintype "passive"))
      (node (ref "C9") (pin "2") (pinfunction "2_2") (pintype "passive"))
      (node (ref "D1") (pin "2") (pinfunction "GND_2") (pintype "bidirectional"))
      (node (ref "D2") (pin "1") (pinfunction "K_1") (pintype "bidirectional"))
      (node (ref "IC1") (pin "D2") (pinfunction "GND_D2") (pintype "bidirectional"))
      (node (ref "IC2") (pin "B1") (pinfunction "VSEL_B1") (pintype "bidirectional"))
      (node (ref "IC2") (pin "C1") (pinfunction "AGND_C1") (pintype "bidirectional"))
      (node (ref "IC2") (pin "C2") (pinfunction "PGND_1_C2") (pintype "bidirectional"))
      (node (ref "IC2") (pin "C3") (pinfunction "PGND_2_C3") (pintype "bidirectional"))
      (node (ref "IC3") (pin "8") (pinfunction "GNDIO_8") (pintype "bidirectional"))
      (node (ref "IC3") (pin "9") (pinfunction "GND_9") (pintype "bidirectional"))
      (node (ref "IC4") (pin "B1") (pinfunction "IN/TRIG_B1") (pintype "bidirectional"))
      (node (ref "IC4") (pin "B3") (pinfunction "GND_B3") (pintype "bidirectional"))
      (node (ref "J1") (pin "17") (pinfunction "17_17") (pintype "bidirectional"))
      (node (ref "J1") (pin "8") (pinfunction "8_8") (pintype "bidirectional"))
      (node (ref "J1") (pin "MP1") (pinfunction "MP1_MP1") (pintype "bidirectional"))
      (node (ref "J1") (pin "MP2") (pinfunction "MP2_MP2") (pintype "bidirectional"))
      (node (ref "J2") (pin "A12_B1") (pinfunction "GND_A12_B1") (pintype "power_in"))
      (node (ref "J2") (pin "A1_B12") (pinfunction "GND_A1_B12") (pintype "power_in"))
      (node (ref "J2") (pin "SH1") (pinfunction "SHIELD_SH1") (pintype "passive"))
      (node (ref "J2") (pin "SH2") (pinfunction "SHIELD_SH2") (pintype "passive"))
      (node (ref "J2") (pin "SH3") (pinfunction "SHIELD_SH3") (pintype "passive"))
      (node (ref "J2") (pin "SH4") (pinfunction "SHIELD_SH4") (pintype "passive"))
      (node (ref "J5") (pin "3") (pinfunction "3_3") (pintype "bidirectional"))
      (node (ref "J5") (pin "5") (pinfunction "5_5") (pintype "bidirectional"))
      (node (ref "R1") (pin "1") (pinfunction "1_1") (pintype "bidirectional"))
      (node (ref "R12") (pin "1") (pinfunction "1_1") (pintype "bidirectional"))
      (node (ref "R14") (pin "1") (pinfunction "1_1") (pintype "bidirectional"))
      (node (ref "R6") (pin "2") (pinfunction "2_2") (pintype "bidirectional"))
      (node (ref "R7") (pin "1") (pinfunction "1_1") (pintype "bidirectional"))
      (node (ref "R8") (pin "2") (pinfunction "2_2") (pintype "bidirectional"))
      (node (ref "SJ2") (pin "1") (pinfunction "1_1") (pintype "passive"))
      (node (ref "SW_DN") (pin "1") (pinfunction "1_1") (pintype "passive"))
      (node (ref "SW_ENT") (pin "1") (pinfunction "1_1") (pintype "passive"))
      (node (ref "SW_UP") (pin "1") (pinfunction "1_1") (pintype "passive"))
      (node (ref "TP_GND") (pin "TP") (pinfunction "TP_TP") (pintype "input"))
      (node (ref "TP_VBAT_GND") (pin "TP") (pinfunction "TP_TP") (pintype "input"))
      (node (ref "U1") (pin "1") (pinfunction "CTG_1") (pintype "power_in"))
      (node (ref "U1") (pin "4") (pinfunction "GND_4") (pintype "power_in"))
      (node (ref "U1") (pin "6") (pinfunction "QSTRT_6") (pintype "input"))
      (node (ref "U1") (pin "9") (pinfunction "EP_9") (pintype "power_in"))
      (node (ref "U2") (pin "P$74") (pinfunction "VSS_PAD_P$74") (pintype "bidirectional"))
      (node (ref "U2") (pin "P$75") (pinfunction "VSS_PAD_P$75") (pintype "bidirectional"))
      (node (ref "U2") (pin "P$76") (pinfunction "VSS_PAD_P$76") (pintype "bidirectional"))
      (node (ref "U2") (pin "P$77") (pinfunction "VSS_PAD_P$77") (pintype "bidirectional"))
      (node (ref "U2") (pin "P$78") (pinfunction "VSS_PAD_P$78") (pintype "bidirectional"))
      (node (ref "U2") (pin "P$79") (pinfunction "VSS_PAD_P$79") (pintype "bidirectional"))
      (node (ref "U2") (pin "P$80") (pinfunction "VSS_PAD_P$80") (pintype "bidirectional"))
      (node (ref "U2") (pin "P$81") (pinfunction "VSS_PAD_P$81") (pintype "bidirectional"))
      (node (ref "U2") (pin "P$82") (pinfunction "VSS_PAD_P$82") (pintype "bidirectional"))
      (node (ref "U2") (pin "P$83") (pinfunction "VSS_PAD_P$83") (pintype "bidirectional"))
      (node (ref "U2") (pin "P$84") (pinfunction "VSS_PAD_P$84") (pintype "bidirectional"))
      (node (ref "U2") (pin "P$85") (pinfunction "VSS_PAD_P$85") (pintype "bidirectional"))
      (node (ref "U2") (pin "P$86") (pinfunction "VSS_PAD_P$86") (pintype "bidirectional"))
      (node (ref "U2") (pin "P$87") (pinfunction "VSS_PAD_P$87") (pintype "bidirectional"))
      (node (ref "U2") (pin "P$88") (pinfunction "VSS_PAD_P$88") (pintype "bidirectional"))
      (node (ref "U2") (pin "P$89") (pinfunction "VSS_PAD_P$89") (pintype "bidirectional"))
      (node (ref "U2") (pin "P$90") (pinfunction "VSS_PAD_P$90") (pintype "bidirectional"))
      (node (ref "U2") (pin "P$B7") (pinfunction "VSS_P$B7") (pintype "power_in"))
      (node (ref "U2") (pin "P$F23") (pinfunction "VSS_PA_P$F23") (pintype "bidirectional"))
      (node (ref "X1") (pin "2") (pinfunction "2_2") (pintype "passive"))
      (node (ref "X1") (pin "4") (pinfunction "4_4") (pintype "passive"))
    )
    (net (code "17") (name "HAPTIC_EN") (class "Default")
      (node (ref "IC4") (pin "A1") (pinfunction "EN_A1") (pintype "bidirectional"))
      (node (ref "U2") (pin "P$G1") (pinfunction "P0.26_P$G1") (pintype "bidirectional"))
    )
    (net (code "18") (name "IMU_INT1") (class "Default")
      (node (ref "IC3") (pin "5") (pinfunction "INT1_5") (pintype "bidirectional"))
      (node (ref "U2") (pin "P$N1") (pinfunction "P0.08_P$N1") (pintype "bidirectional"))
    )
    (net (code "19") (name "IMU_INT2") (class "Default")
      (node (ref "IC3") (pin "6") (pinfunction "INT2_6") (pintype "bidirectional"))
      (node (ref "U2") (pin "P$P2") (pinfunction "P1.08_P$P2") (pintype "bidirectional"))
    )
    (net (code "20") (name "LX1") (class "Default")
      (node (ref "IC2") (pin "B2") (pinfunction "SW1_1_B2") (pintype "bidirectional"))
      (node (ref "IC2") (pin "B3") (pinfunction "SW1_2_B3") (pintype "bidirectional"))
      (node (ref "L1") (pin "1") (pinfunction "1_1") (pintype "bidirectional"))
    )
    (net (code "21") (name "LX2") (class "Default")
      (node (ref "IC2") (pin "D2") (pinfunction "SW2_1_D2") (pintype "bidirectional"))
      (node (ref "IC2") (pin "D3") (pinfunction "SW2_2_D3") (pintype "bidirectional"))
      (node (ref "L1") (pin "2") (pinfunction "2_2") (pintype "bidirectional"))
    )
    (net (code "22") (name "MOSI") (class "Default")
      (node (ref "J1") (pin "14") (pinfunction "14_14") (pintype "bidirectional"))
      (node (ref "U2") (pin "P$AD20") (pinfunction "P0.24_P$AD20") (pintype "bidirectional"))
    )
    (net (code "23") (name "Net-(ANT1-FEED)") (class "Default")
      (node (ref "ANT1") (pin "1") (pinfunction "FEED_1") (pintype "input"))
      (node (ref "C40") (pin "1") (pinfunction "1_1") (pintype "passive"))
      (node (ref "C41") (pin "1") (pinfunction "1_1") (pintype "passive"))
      (node (ref "L5") (pin "2") (pinfunction "2_2") (pintype "bidirectional"))
    )
    (net (code "24") (name "Net-(C19-Pad2)") (class "Default")
      (node (ref "C19") (pin "2") (pinfunction "2_2") (pintype "passive"))
      (node (ref "J1") (pin "4") (pinfunction "4_4") (pintype "bidirectional"))
    )
    (net (code "25") (name "Net-(C20-Pad2)") (class "Default")
      (node (ref "C20") (pin "2") (pinfunction "2_2") (pintype "passive"))
      (node (ref "J1") (pin "5") (pinfunction "5_5") (pintype "bidirectional"))
    )
    (net (code "26") (name "Net-(C22-Pad2)") (class "Default")
      (node (ref "C22") (pin "2") (pinfunction "2_2") (pintype "passive"))
      (node (ref "J1") (pin "22") (pinfunction "22_22") (pintype "bidirectional"))
    )
    (net (code "27") (name "Net-(C23-Pad2)") (class "Default")
      (node (ref "C23") (pin "2") (pinfunction "2_2") (pintype "passive"))
      (node (ref "J1") (pin "18") (pinfunction "18_18") (pintype "bidirectional"))
    )
    (net (code "28") (name "Net-(C24-Pad2)") (class "Default")
      (node (ref "C24") (pin "2") (pinfunction "2_2") (pintype "passive"))
      (node (ref "J1") (pin "19") (pinfunction "19_19") (pintype "bidirectional"))
    )
    (net (code "29") (name "Net-(C25-Pad2)") (class "Default")
      (node (ref "C25") (pin "2") (pinfunction "2_2") (pintype "passive"))
      (node (ref "J1") (pin "20") (pinfunction "20_20") (pintype "bidirectional"))
    )
    (net (code "30") (name "Net-(C28-Pad2)") (class "Default")
      (node (ref "C28") (pin "2") (pinfunction "2_2") (pintype "passive"))
      (node (ref "J1") (pin "24") (pinfunction "24_24") (pintype "bidirectional"))
    )
    (net (code "31") (name "Net-(D2-A)") (class "Default")
      (node (ref "C17") (pin "1") (pinfunction "1_1") (pintype "passive"))
      (node (ref "D2") (pin "2") (pinfunction "A_2") (pintype "bidirectional"))
      (node (ref "D3") (pin "1") (pinfunction "K_1") (pintype "bidirectional"))
    )
    (net (code "32") (name "Net-(D4-A)") (class "Default")
      (node (ref "C17") (pin "2") (pinfunction "2_2") (pintype "passive"))
      (node (ref "D4") (pin "2") (pinfunction "A_2") (pintype "bidirectional"))
      (node (ref "L2") (pin "2") (pinfunction "2_2") (pintype "passive"))
      (node (ref "Q1") (pin "3") (pinfunction "D_3") (pintype "bidirectional"))
    )
    (net (code "33") (name "Net-(IC1-TS{slash}MR)") (class "Default")
      (node (ref "IC1") (pin "D1") (pinfunction "TS/MR_D1") (pintype "bidirectional"))
      (node (ref "R1") (pin "2") (pinfunction "2_2") (pintype "bidirectional"))
    )
    (net (code "34") (name "Net-(IC2-SCL)") (class "Default")
      (node (ref "IC2") (pin "D1") (pinfunction "SCL_D1") (pintype "bidirectional"))
      (node (ref "R2") (pin "1") (pinfunction "1_1") (pintype "bidirectional"))
    )
    (net (code "35") (name "Net-(IC2-SDA)") (class "Default")
      (node (ref "IC2") (pin "E1") (pinfunction "SDA_E1") (pintype "bidirectional"))
      (node (ref "R3") (pin "1") (pinfunction "1_1") (pintype "bidirectional"))
    )
    (net (code "36") (name "Net-(IC3-SDO)") (class "Default")
      (node (ref "IC3") (pin "1") (pinfunction "SDO_1") (pintype "bidirectional"))
      (node (ref "R6") (pin "1") (pinfunction "1_1") (pintype "bidirectional"))
    )
    (net (code "37") (name "Net-(IC4-REG)") (class "Default")
      (node (ref "C11") (pin "1") (pinfunction "1_1") (pintype "passive"))
      (node (ref "IC4") (pin "A2") (pinfunction "REG_A2") (pintype "bidirectional"))
    )
    (net (code "38") (name "Net-(J2-CC1)") (class "Default")
      (node (ref "J2") (pin "A5") (pinfunction "CC1_A5") (pintype "bidirectional"))
      (node (ref "R7") (pin "2") (pinfunction "2_2") (pintype "bidirectional"))
    )
    (net (code "39") (name "Net-(J2-CC2)") (class "Default")
      (node (ref "J2") (pin "B5") (pinfunction "CC2_B5") (pintype "bidirectional"))
      (node (ref "R8") (pin "1") (pinfunction "1_1") (pintype "bidirectional"))
    )
    (net (code "40") (name "Net-(L3-Pad2)") (class "Default")
      (node (ref "L3") (pin "2") (pinfunction "2_2") (pintype "bidirectional"))
      (node (ref "L4") (pin "1") (pinfunction "1_1") (pintype "bidirectional"))
    )
    (net (code "41") (name "Net-(R13-Pad1)") (class "Default")
      (node (ref "R13") (pin "1") (pinfunction "1_1") (pintype "bidirectional"))
      (node (ref "R14") (pin "2") (pinfunction "2_2") (pintype "bidirectional"))
      (node (ref "SJ2") (pin "2") (pinfunction "2_2") (pintype "passive"))
    )
    (net (code "42") (name "Net-(U2-ANT)") (class "Default")
      (node (ref "C39") (pin "1") (pinfunction "1_1") (pintype "passive"))
      (node (ref "L5") (pin "1") (pinfunction "1_1") (pintype "bidirectional"))
      (node (ref "U2") (pin "P$H23") (pinfunction "ANT_P$H23") (pintype "bidirectional"))
    )
    (net (code "43") (name "Net-(U2-DCC)") (class "Default")
      (node (ref "L3") (pin "1") (pinfunction "1_1") (pintype "bidirectional"))
      (node (ref "U2") (pin "P$B3") (pinfunction "DCC_P$B3") (pintype "output"))
    )
    (net (code "44") (name "Net-(U2-DEC1)") (class "Default")
      (node (ref "C30") (pin "2") (pinfunction "2_2") (pintype "passive"))
      (node (ref "U2") (pin "P$C1") (pinfunction "DEC1_P$C1") (pintype "power_in"))
    )
    (net (code "45") (name "Net-(U2-DEC2)") (class "Default")
      (node (ref "C33") (pin "1") (pinfunction "1_1") (pintype "passive"))
      (node (ref "U2") (pin "P$A18") (pinfunction "DEC2_P$A18") (pintype "bidirectional"))
    )
    (net (code "46") (name "Net-(U2-DEC3)") (class "Default")
      (node (ref "C37") (pin "1") (pinfunction "1_1") (pintype "passive"))
      (node (ref "U2") (pin "P$D23") (pinfunction "DEC3_P$D23") (pintype "bidirectional"))
    )
    (net (code "47") (name "Net-(U2-DEC3V3)") (class "Default")
      (node (ref "C46") (pin "1") (pinfunction "1_1") (pintype "passive"))
      (node (ref "U2") (pin "P$AC5") (pinfunction "DEC3V3_P$AC5") (pintype "bidirectional"))
    )
    (net (code "48") (name "Net-(U2-DEC4)") (class "Default")
      (node (ref "C31") (pin "1") (pinfunction "1_1") (pintype "passive"))
      (node (ref "C32") (pin "1") (pinfunction "1_1") (pintype "passive"))
      (node (ref "C38") (pin "1") (pinfunction "1_1") (pintype "passive"))
      (node (ref "L4") (pin "2") (pinfunction "2_2") (pintype "bidirectional"))
      (node (ref "U2") (pin "P$B5") (pinfunction "DEC4_P$B5") (pintype "power_in"))
      (node (ref "U2") (pin "P$E24") (pinfunction "DEC6_P$E24") (pintype "bidirectional"))
    )
    (net (code "49") (name "Net-(U2-DEC5)") (class "Default")
      (node (ref "C42") (pin "1") (pinfunction "1_1") (pintype "passive"))
      (node (ref "U2") (pin "P$N24") (pinfunction "DEC5_P$N24") (pintype "bidirectional"))
    )
    (net (code "50") (name "Net-(U2-P0.00{slash}XL1)") (class "Default")
      (node (ref "C48") (pin "2") (pinfunction "2_2") (pintype "passive"))
      (node (ref "U2") (pin "P$D2") (pinfunction "P0.00/XL1_P$D2") (pintype "bidirectional"))
      (node (ref "X2") (pin "2") (pinfunction "2_2") (pintype "passive"))
    )
    (net (code "51") (name "Net-(U2-P0.01{slash}XL2)") (class "Default")
      (node (ref "C49") (pin "2") (pinfunction "2_2") (pintype "passive"))
      (node (ref "U2") (pin "P$F2") (pinfunction "P0.01/XL2_P$F2") (pintype "bidirectional"))
      (node (ref "X2") (pin "1") (pinfunction "1_1") (pintype "passive"))
    )
    (net (code "52") (name "Net-(U2-XC1)") (class "Default")
      (node (ref "C36") (pin "1") (pinfunction "1_1") (pintype "passive"))
      (node (ref "U2") (pin "P$B24") (pinfunction "XC1_P$B24") (pintype "input"))
      (node (ref "X1") (pin "1") (pinfunction "1_1") (pintype "passive"))
    )
    (net (code "53") (name "Net-(U2-XC2)") (class "Default")
      (node (ref "C35") (pin "1") (pinfunction "1_1") (pintype "passive"))
      (node (ref "U2") (pin "P$A23") (pinfunction "XC2_P$A23") (pintype "output"))
      (node (ref "X1") (pin "3") (pinfunction "3_3") (pintype "passive"))
    )
    (net (code "54") (name "OUT+") (class "Default")
      (node (ref "IC4") (pin "A3") (pinfunction "OUT+_A3") (pintype "bidirectional"))
      (node (ref "TP_OUT+") (pin "TP") (pinfunction "TP_TP") (pintype "input"))
    )
    (net (code "55") (name "OUT-") (class "Default")
      (node (ref "IC4") (pin "C3") (pinfunction "OUT-_C3") (pintype "bidirectional"))
      (node (ref "TP_OUT-") (pin "TP") (pinfunction "TP_TP") (pintype "input"))
    )
    (net (code "56") (name "P0.22") (class "Default")
      (node (ref "Q2") (pin "1") (pinfunction "G_1") (pintype "bidirectional"))
      (node (ref "R15") (pin "1") (pinfunction "1_1") (pintype "bidirectional"))
      (node (ref "U2") (pin "P$AD18") (pinfunction "P0.22_P$AD18") (pintype "bidirectional"))
    )
    (net (code "57") (name "PMIC_INT") (class "Default")
      (node (ref "IC1") (pin "A1") (pinfunction "~{INT}_A1") (pintype "bidirectional"))
      (node (ref "U2") (pin "P$K2") (pinfunction "P0.05/AIN3_P$K2") (pintype "bidirectional"))
    )
    (net (code "58") (name "PREVGH") (class "Default")
      (node (ref "C26") (pin "2") (pinfunction "2_2") (pintype "passive"))
      (node (ref "D4") (pin "1") (pinfunction "K_1") (pintype "bidirectional"))
      (node (ref "J1") (pin "21") (pinfunction "21_21") (pintype "bidirectional"))
    )
    (net (code "59") (name "PREVGL") (class "Default")
      (node (ref "C27") (pin "2") (pinfunction "2_2") (pintype "passive"))
      (node (ref "D3") (pin "2") (pinfunction "A_2") (pintype "bidirectional"))
      (node (ref "J1") (pin "23") (pinfunction "23_23") (pintype "bidirectional"))
    )
    (net (code "60") (name "RESE") (class "Default")
      (node (ref "J1") (pin "3") (pinfunction "3_3") (pintype "bidirectional"))
      (node (ref "Q1") (pin "2") (pinfunction "S_2") (pintype "bidirectional"))
      (node (ref "R13") (pin "2") (pinfunction "2_2") (pintype "bidirectional"))
    )
    (net (code "61") (name "RESET") (class "Default")
      (node (ref "J5") (pin "6") (pinfunction "6_6") (pintype "bidirectional"))
      (node (ref "TP_RESET") (pin "TP") (pinfunction "TP_TP") (pintype "input"))
      (node (ref "U2") (pin "P$AC13") (pinfunction "P0.18/RESET_P$AC13") (pintype "bidirectional"))
    )
    (net (code "62") (name "SCK") (class "Default")
      (node (ref "J1") (pin "13") (pinfunction "13_13") (pintype "bidirectional"))
      (node (ref "U2") (pin "P$AC21") (pinfunction "P0.25_P$AC21") (pintype "bidirectional"))
    )
    (net (code "63") (name "SCL") (class "Default")
      (node (ref "IC1") (pin "B1") (pinfunction "SCL_B1") (pintype "bidirectional"))
      (node (ref "IC3") (pin "12") (pinfunction "SCX_12") (pintype "bidirectional"))
      (node (ref "IC4") (pin "C1") (pinfunction "SCL_C1") (pintype "bidirectional"))
      (node (ref "R2") (pin "2") (pinfunction "2_2") (pintype "bidirectional"))
      (node (ref "R4") (pin "2") (pinfunction "2_2") (pintype "bidirectional"))
      (node (ref "U1") (pin "7") (pinfunction "SCL_7") (pintype "input"))
      (node (ref "U2") (pin "P$R1") (pinfunction "P1.09_P$R1") (pintype "bidirectional"))
    )
    (net (code "64") (name "SDA") (class "Default")
      (node (ref "IC1") (pin "C1") (pinfunction "SDA_C1") (pintype "bidirectional"))
      (node (ref "IC3") (pin "2") (pinfunction "SDX_2") (pintype "bidirectional"))
      (node (ref "IC4") (pin "B2") (pinfunction "SDA_B2") (pintype "bidirectional"))
      (node (ref "R3") (pin "2") (pinfunction "2_2") (pintype "bidirectional"))
      (node (ref "R5") (pin "2") (pinfunction "2_2") (pintype "bidirectional"))
      (node (ref "U1") (pin "8") (pinfunction "SDA_8") (pintype "bidirectional"))
      (node (ref "U2") (pin "P$L1") (pinfunction "P0.06_P$L1") (pintype "bidirectional"))
    )
    (net (code "65") (name "SWCLK") (class "Default")
      (node (ref "J5") (pin "4") (pinfunction "4_4") (pintype "bidirectional"))
      (node (ref "TP_SWCLK") (pin "TP") (pinfunction "TP_TP") (pintype "input"))
      (node (ref "U2") (pin "P$AA24") (pinfunction "SWDCLK_P$AA24") (pintype "input"))
    )
    (net (code "66") (name "SWDIO") (class "Default")
      (node (ref "J5") (pin "2") (pinfunction "2_2") (pintype "bidirectional"))
      (node (ref "TP_SWDIO") (pin "TP") (pinfunction "TP_TP") (pintype "input"))
      (node (ref "U2") (pin "P$AC24") (pinfunction "SWDIO_P$AC24") (pintype "bidirectional"))
    )
    (net (code "67") (name "SWO") (class "Default")
      (node (ref "TP_SWO") (pin "TP") (pinfunction "TP_TP") (pintype "input"))
      (node (ref "U2") (pin "P$AD22") (pinfunction "P1.00_P$AD22") (pintype "bidirectional"))
    )
    (net (code "68") (name "VBAT") (class "Default")
      (node (ref "C3") (pin "1") (pinfunction "1_1") (pintype "passive"))
      (node (ref "C9") (pin "1") (pinfunction "1_1") (pintype "passive"))
      (node (ref "IC1") (pin "C2") (pinfunction "BAT_C2") (pintype "bidirectional"))
      (node (ref "TP_VBAT") (pin "TP") (pinfunction "TP_TP") (pintype "input"))
      (node (ref "U1") (pin "2") (pinfunction "CELL_2") (pintype "power_in"))
      (node (ref "U1") (pin "3") (pinfunction "VDD_3") (pintype "power_in"))
    )
    (net (code "69") (name "VBUS") (class "Default")
      (node (ref "C1") (pin "1") (pinfunction "1_1") (pintype "passive"))
      (node (ref "C12") (pin "2") (pinfunction "2_2") (pintype "passive"))
      (node (ref "C13") (pin "2") (pinfunction "2_2") (pintype "passive"))
      (node (ref "C45") (pin "1") (pinfunction "1_1") (pintype "passive"))
      (node (ref "D1") (pin "5") (pinfunction "VBUS_5") (pintype "bidirectional"))
      (node (ref "IC1") (pin "A2") (pinfunction "IN_A2") (pintype "bidirectional"))
      (node (ref "J2") (pin "A4_B9") (pinfunction "VBUS_A4_B9") (pintype "power_in"))
      (node (ref "J2") (pin "A9_B4") (pinfunction "VBUS_A9_B4") (pintype "power_in"))
      (node (ref "U2") (pin "P$AD2") (pinfunction "VBUS_P$AD2") (pintype "power_in"))
    )
    (net (code "70") (name "VREG") (class "Default")
      (node (ref "C2") (pin "1") (pinfunction "1_1") (pintype "passive"))
      (node (ref "C4") (pin "2") (pinfunction "2_2") (pintype "passive"))
      (node (ref "C5") (pin "1") (pinfunction "1_1") (pintype "passive"))
      (node (ref "IC1") (pin "B2") (pinfunction "SYS_B2") (pintype "bidirectional"))
      (node (ref "IC2") (pin "A1") (pinfunction "EN_A1") (pintype "bidirectional"))
      (node (ref "IC2") (pin "A2") (pinfunction "VIN_1_A2") (pintype "bidirectional"))
      (node (ref "IC2") (pin "A3") (pinfunction "VIN_2_A3") (pintype "bidirectional"))
      (node (ref "TP_VREG") (pin "TP") (pinfunction "TP_TP") (pintype "input"))
    )
    (net (code "71") (name "unconnected-(ANT1-NC-Pad2)") (class "Default")
      (node (ref "ANT1") (pin "2") (pinfunction "NC_2") (pintype "no_connect"))
    )
    (net (code "72") (name "unconnected-(IC3-ASCL-Pad11)") (class "Default")
      (node (ref "IC3") (pin "11") (pinfunction "ASCL_11") (pintype "bidirectional"))
    )
    (net (code "73") (name "unconnected-(IC3-ASDA-Pad4)") (class "Default")
      (node (ref "IC3") (pin "4") (pinfunction "ASDA_4") (pintype "bidirectional"))
    )
    (net (code "74") (name "unconnected-(J1-Pad1)") (class "Default")
      (node (ref "J1") (pin "1") (pinfunction "1_1") (pintype "bidirectional"))
    )
    (net (code "75") (name "unconnected-(J1-Pad6)") (class "Default")
      (node (ref "J1") (pin "6") (pinfunction "6_6") (pintype "bidirectional"))
    )
    (net (code "76") (name "unconnected-(J1-Pad7)") (class "Default")
      (node (ref "J1") (pin "7") (pinfunction "7_7") (pintype "bidirectional"))
    )
    (net (code "77") (name "unconnected-(J2-SBU1-PadA8)") (class "Default")
      (node (ref "J2") (pin "A8") (pinfunction "SBU1_A8") (pintype "bidirectional"))
    )
    (net (code "78") (name "unconnected-(J2-SBU2-PadB8)") (class "Default")
      (node (ref "J2") (pin "B8") (pinfunction "SBU2_B8") (pintype "bidirectional"))
    )
    (net (code "79") (name "unconnected-(U2-DCCH-PadP$AB2)") (class "Default")
      (node (ref "U2") (pin "P$AB2") (pinfunction "DCCH_P$AB2") (pintype "bidirectional"))
    )
    (net (code "80") (name "unconnected-(U2-P0.02{slash}AIN0-PadP$A12)") (class "Default")
      (node (ref "U2") (pin "P$A12") (pinfunction "P0.02/AIN0_P$A12") (pintype "bidirectional"))
    )
    (net (code "81") (name "unconnected-(U2-P0.03{slash}AIN1-PadP$B13)") (class "Default")
      (node (ref "U2") (pin "P$B13") (pinfunction "P0.03/AIN1_P$B13") (pintype "bidirectional"))
    )
    (net (code "82") (name "unconnected-(U2-P0.04{slash}AIN2-PadP$J1)") (class "Default")
      (node (ref "U2") (pin "P$J1") (pinfunction "P0.04/AIN2_P$J1") (pintype "bidirectional"))
    )
    (net (code "83") (name "unconnected-(U2-P0.07-PadP$M2)") (class "Default")
      (node (ref "U2") (pin "P$M2") (pinfunction "P0.07_P$M2") (pintype "bidirectional"))
    )
    (net (code "84") (name "unconnected-(U2-P0.09{slash}NFC1-PadP$L24)") (class "Default")
      (node (ref "U2") (pin "P$L24") (pinfunction "P0.09/NFC1_P$L24") (pintype "bidirectional"))
    )
    (net (code "85") (name "unconnected-(U2-P0.10{slash}NFC2-PadP$J24)") (class "Default")
      (node (ref "U2") (pin "P$J24") (pinfunction "P0.10/NFC2_P$J24") (pintype "bidirectional"))
    )
    (net (code "86") (name "unconnected-(U2-P0.11-PadP$T2)") (class "Default")
      (node (ref "U2") (pin "P$T2") (pinfunction "P0.11_P$T2") (pintype "bidirectional"))
    )
    (net (code "87") (name "unconnected-(U2-P0.13-PadP$AD8)") (class "Default")
      (node (ref "U2") (pin "P$AD8") (pinfunction "P0.13_P$AD8") (pintype "bidirectional"))
    )
    (net (code "88") (name "unconnected-(U2-P0.14-PadP$AC9)") (class "Default")
      (node (ref "U2") (pin "P$AC9") (pinfunction "P0.14_P$AC9") (pintype "bidirectional"))
    )
    (net (code "89") (name "unconnected-(U2-P0.19-PadP$AC15)") (class "Default")
      (node (ref "U2") (pin "P$AC15") (pinfunction "P0.19_P$AC15") (pintype "bidirectional"))
    )
    (net (code "90") (name "unconnected-(U2-P0.21-PadP$AC17)") (class "Default")
      (node (ref "U2") (pin "P$AC17") (pinfunction "P0.21_P$AC17") (pintype "bidirectional"))
    )
    (net (code "91") (name "unconnected-(U2-P0.23-PadP$AC19)") (class "Default")
      (node (ref "U2") (pin "P$AC19") (pinfunction "P0.23_P$AC19") (pintype "bidirectional"))
    )
    (net (code "92") (name "unconnected-(U2-P0.27-PadP$H2)") (class "Default")
      (node (ref "U2") (pin "P$H2") (pinfunction "P0.27_P$H2") (pintype "bidirectional"))
    )
    (net (code "93") (name "unconnected-(U2-P0.28{slash}AIN4-PadP$B11)") (class "Default")
      (node (ref "U2") (pin "P$B11") (pinfunction "P0.28/AIN4_P$B11") (pintype "bidirectional"))
    )
    (net (code "94") (name "unconnected-(U2-P0.29{slash}AIN5-PadP$A10)") (class "Default")
      (node (ref "U2") (pin "P$A10") (pinfunction "P0.29/AIN5_P$A10") (pintype "bidirectional"))
    )
    (net (code "95") (name "unconnected-(U2-P0.30{slash}AIN6-PadP$B9)") (class "Default")
      (node (ref "U2") (pin "P$B9") (pinfunction "P0.30/AIN6_P$B9") (pintype "bidirectional"))
    )
    (net (code "96") (name "unconnected-(U2-P0.31{slash}AIN7-PadP$A8)") (class "Default")
      (node (ref "U2") (pin "P$A8") (pinfunction "P0.31/AIN7_P$A8") (pintype "bidirectional"))
    )
    (net (code "97") (name "unconnected-(U2-P1.01-PadP$Y23)") (class "Default")
      (node (ref "U2") (pin "P$Y23") (pinfunction "P1.01_P$Y23") (pintype "bidirectional"))
    )
    (net (code "98") (name "unconnected-(U2-P1.03-PadP$V23)") (class "Default")
      (node (ref "U2") (pin "P$V23") (pinfunction "P1.03_P$V23") (pintype "bidirectional"))
    )
    (net (code "99") (name "unconnected-(U2-P1.05-PadP$T23)") (class "Default")
      (node (ref "U2") (pin "P$T23") (pinfunction "P1.05_P$T23") (pintype "bidirectional"))
    )
    (net (code "100") (name "unconnected-(U2-P1.07-PadP$P23)") (class "Default")
      (node (ref "U2") (pin "P$P23") (pinfunction "P1.07_P$P23") (pintype "bidirectional"))
    )
    (net (code "101") (name "unconnected-(U2-P1.10-PadP$A20)") (class "Default")
      (node (ref "U2") (pin "P$A20") (pinfunction "P1.10_P$A20") (pintype "bidirectional"))
    )
    (net (code "102") (name "unconnected-(U2-P1.11-PadP$B19)") (class "Default")
      (node (ref "U2") (pin "P$B19") (pinfunction "P1.11_P$B19") (pintype "bidirectional"))
    )
    (net (code "103") (name "unconnected-(U2-P1.12-PadP$B17)") (class "Default")
      (node (ref "U2") (pin "P$B17") (pinfunction "P1.12_P$B17") (pintype "bidirectional"))
    )
    (net (code "104") (name "unconnected-(U2-P1.13-PadP$A16)") (class "Default")
      (node (ref "U2") (pin "P$A16") (pinfunction "P1.13_P$A16") (pintype "bidirectional"))
    )
    (net (code "105") (name "unconnected-(U2-P1.14-PadP$B15)") (class "Default")
      (node (ref "U2") (pin "P$B15") (pinfunction "P1.14_P$B15") (pintype "bidirectional"))
    )
    (net (code "106") (name "unconnected-(U2-P1.15-PadP$A14)") (class "Default")
      (node (ref "U2") (pin "P$A14") (pinfunction "P1.15_P$A14") (pintype "bidirectional"))
    )
  )
)
